# tail.net
KiCad netlist of a schematic drawn in EAGLE
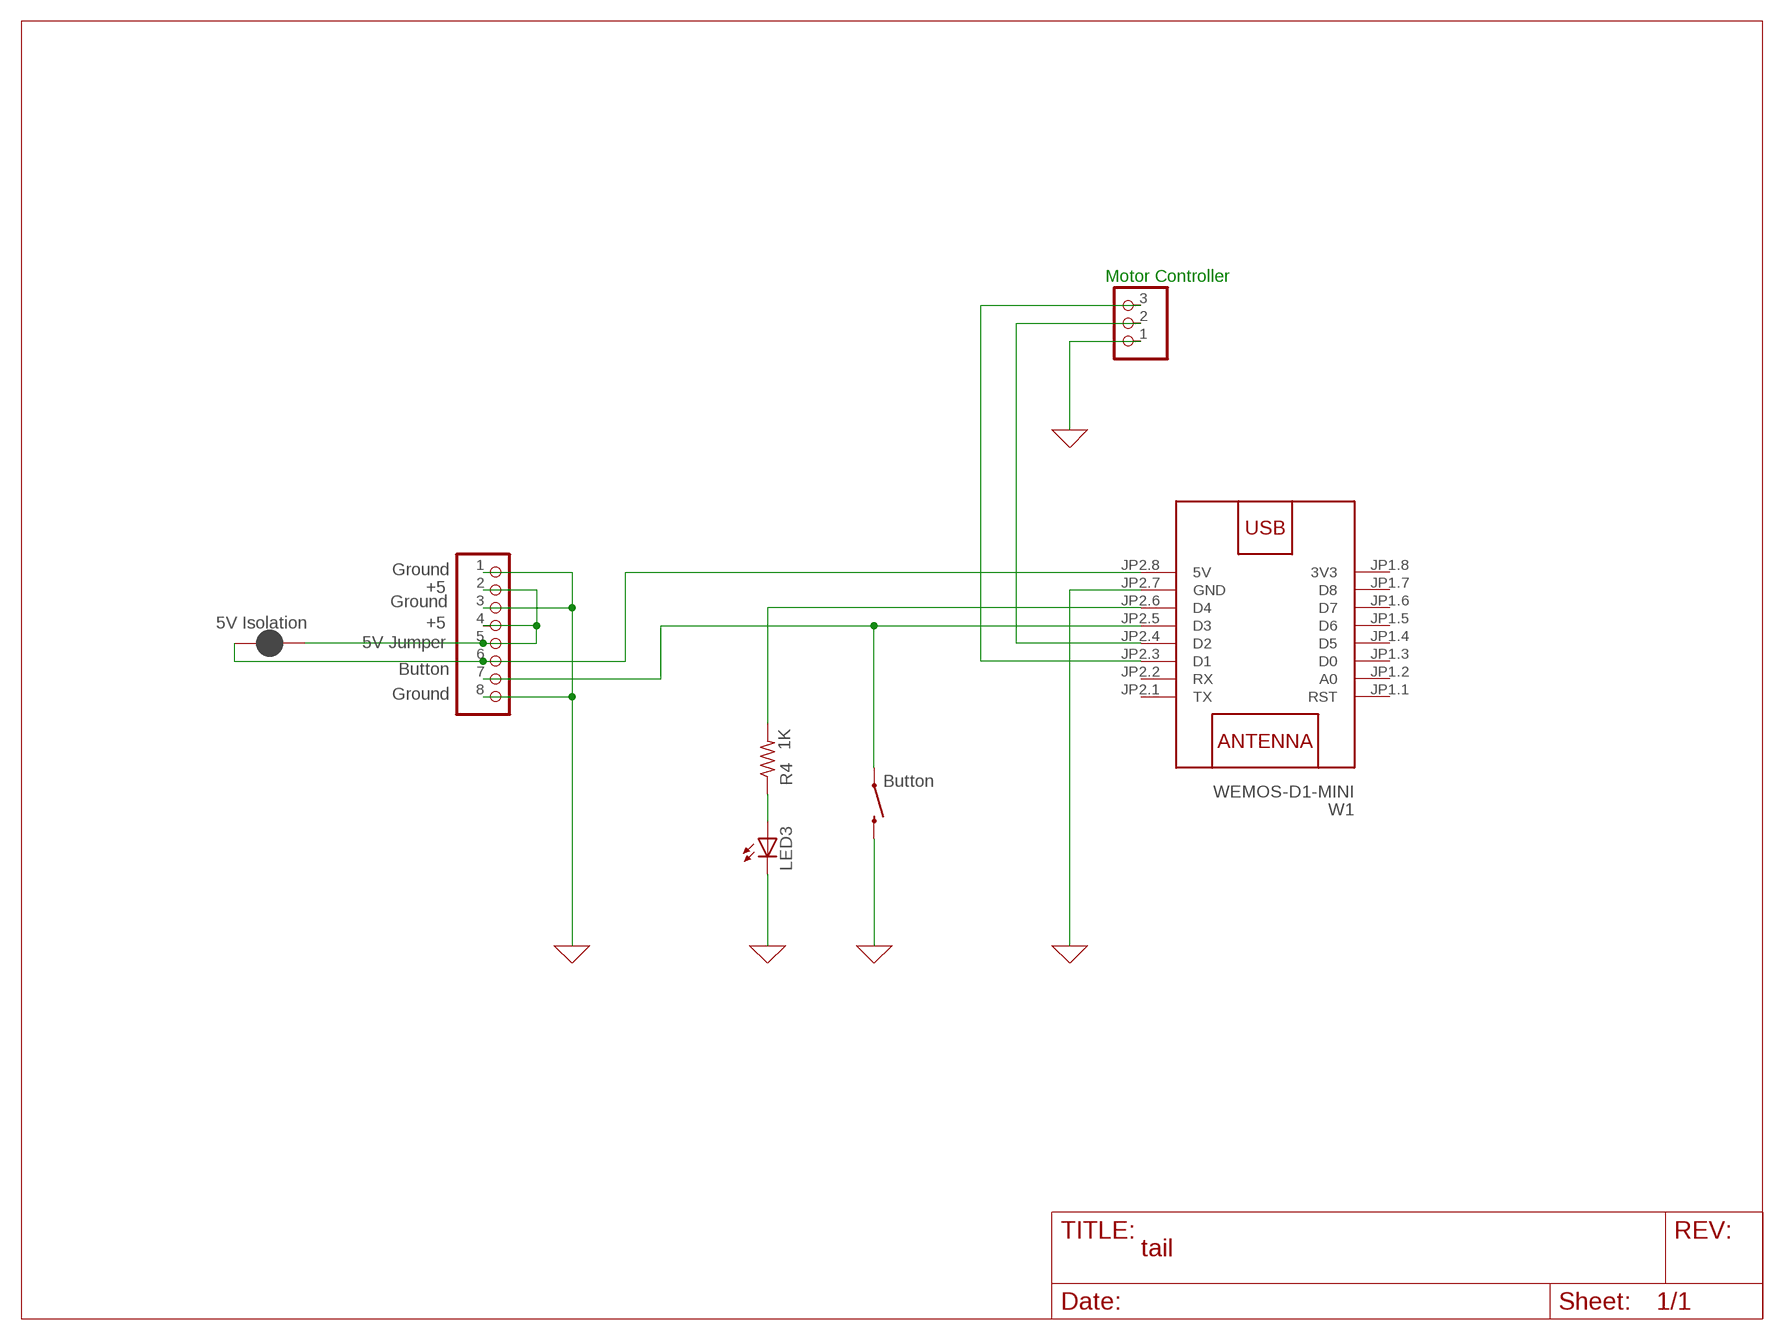
[diagram p0: schematic, sheet 1]

(export (version "E")
  (design (tool "Eeschema 10.0.6"))
  (components
    (comp (ref "JP1")
      (value "PINHD-1X8BIG")
      (footprint "eagle-import:1X08-BIG")
      (libsource (lib "eagle-import") (part "PINHD-1X8BIG"))
    )
    (comp (ref "JP2")
      (value "PINHD-1X3")
      (footprint "eagle-import:1X03")
      (libsource (lib "eagle-import") (part "PINHD-1X3"))
    )
    (comp (ref "JP3")
      (value "JUMPER-SMT_2_NC_PASTE_NO-SILK")
      (footprint "eagle-import:SMT-JUMPER_2_NC_PASTE_NO-SILK")
      (libsource (lib "eagle-import") (part "JUMPER-SMT_2_NC_PASTE_NO-SILK"))
    )
    (comp (ref "LED3")
      (value "LED5MM")
      (footprint "eagle-import:LED5MM")
      (libsource (lib "eagle-import") (part "LED5MM"))
    )
    (comp (ref "R4")
      (value "1K")
      (footprint "eagle-import:0207_10")
      (libsource (lib "eagle-import") (part "R-US_0207/10"))
    )
    (comp (ref "S1")
      (value "MOMENTARY-SWITCH-SPST-PTH-6.0MM")
      (footprint "eagle-import:TACTILE_SWITCH_PTH_6.0MM")
      (libsource (lib "eagle-import") (part "MOMENTARY-SWITCH-SPST-PTH-6.0MM"))
    )
    (comp (ref "W1")
      (value "WEMOS-D1-MINI")
      (footprint "eagle-import:WEMOS-D1-MINI")
      (libsource (lib "eagle-import") (part "WEMOS-D1-MINI"))
    )
  )
  (nets
    (net (code "1") (name "/3V3") (class "Default")
      (node (ref "W1") (pin "JP1.8") (pinfunction "3V3_JP1.8") (pintype "power_in"))
    )
    (net (code "2") (name "GND") (class "Default")
      (node (ref "JP1") (pin "1") (pinfunction "1_1") (pintype "passive"))
      (node (ref "JP1") (pin "3") (pinfunction "3_3") (pintype "passive"))
      (node (ref "JP1") (pin "8") (pinfunction "8_8") (pintype "passive"))
      (node (ref "JP2") (pin "1") (pinfunction "1_1") (pintype "passive"))
      (node (ref "LED3") (pin "K") (pinfunction "C_K") (pintype "passive"))
      (node (ref "S1") (pin "3") (pinfunction "2_3") (pintype "passive"))
      (node (ref "W1") (pin "JP2.7") (pinfunction "GND_JP2.7") (pintype "power_in"))
    )
    (net (code "3") (name "Net-(JP1-Pad2)") (class "Default")
      (node (ref "JP1") (pin "2") (pinfunction "2_2") (pintype "passive"))
      (node (ref "JP1") (pin "4") (pinfunction "4_4") (pintype "passive"))
      (node (ref "JP1") (pin "5") (pinfunction "5_5") (pintype "passive"))
      (node (ref "JP3") (pin "2") (pinfunction "2_2") (pintype "passive"))
    )
    (net (code "4") (name "Net-(LED3-PadA)") (class "Default")
      (node (ref "LED3") (pin "A") (pinfunction "A_A") (pintype "passive"))
      (node (ref "R4") (pin "1") (pinfunction "1_1") (pintype "passive"))
    )
    (net (code "5") (name "Net-(W1-5V)") (class "Default")
      (node (ref "JP1") (pin "6") (pinfunction "6_6") (pintype "passive"))
      (node (ref "JP3") (pin "1") (pinfunction "1_1") (pintype "passive"))
      (node (ref "W1") (pin "JP2.8") (pinfunction "5V_JP2.8") (pintype "power_in"))
    )
    (net (code "6") (name "Net-(W1-D1)") (class "Default")
      (node (ref "JP2") (pin "3") (pinfunction "3_3") (pintype "passive"))
      (node (ref "W1") (pin "JP2.3") (pinfunction "D1_JP2.3") (pintype "bidirectional"))
    )
    (net (code "7") (name "Net-(W1-D2)") (class "Default")
      (node (ref "JP2") (pin "2") (pinfunction "2_2") (pintype "passive"))
      (node (ref "W1") (pin "JP2.4") (pinfunction "D2_JP2.4") (pintype "bidirectional"))
    )
    (net (code "8") (name "Net-(W1-D3)") (class "Default")
      (node (ref "JP1") (pin "7") (pinfunction "7_7") (pintype "passive"))
      (node (ref "S1") (pin "1") (pinfunction "1_1") (pintype "passive"))
      (node (ref "W1") (pin "JP2.5") (pinfunction "D3_JP2.5") (pintype "bidirectional"))
    )
    (net (code "9") (name "Net-(W1-D4)") (class "Default")
      (node (ref "R4") (pin "2") (pinfunction "2_2") (pintype "passive"))
      (node (ref "W1") (pin "JP2.6") (pinfunction "D4_JP2.6") (pintype "bidirectional"))
    )
    (net (code "10") (name "unconnected-(W1-A0-PadJP1.2)") (class "Default")
      (node (ref "W1") (pin "JP1.2") (pinfunction "A0_JP1.2") (pintype "bidirectional"))
    )
    (net (code "11") (name "unconnected-(W1-D0-PadJP1.3)") (class "Default")
      (node (ref "W1") (pin "JP1.3") (pinfunction "D0_JP1.3") (pintype "bidirectional"))
    )
    (net (code "12") (name "unconnected-(W1-D5-PadJP1.4)") (class "Default")
      (node (ref "W1") (pin "JP1.4") (pinfunction "D5_JP1.4") (pintype "bidirectional"))
    )
    (net (code "13") (name "unconnected-(W1-D6-PadJP1.5)") (class "Default")
      (node (ref "W1") (pin "JP1.5") (pinfunction "D6_JP1.5") (pintype "bidirectional"))
    )
    (net (code "14") (name "unconnected-(W1-D7-PadJP1.6)") (class "Default")
      (node (ref "W1") (pin "JP1.6") (pinfunction "D7_JP1.6") (pintype "bidirectional"))
    )
    (net (code "15") (name "unconnected-(W1-D8-PadJP1.7)") (class "Default")
      (node (ref "W1") (pin "JP1.7") (pinfunction "D8_JP1.7") (pintype "bidirectional"))
    )
    (net (code "16") (name "unconnected-(W1-RST-PadJP1.1)") (class "Default")
      (node (ref "W1") (pin "JP1.1") (pinfunction "RST_JP1.1") (pintype "bidirectional"))
    )
    (net (code "17") (name "unconnected-(W1-RX-PadJP2.2)") (class "Default")
      (node (ref "W1") (pin "JP2.2") (pinfunction "RX_JP2.2") (pintype "bidirectional"))
    )
    (net (code "18") (name "unconnected-(W1-TX-PadJP2.1)") (class "Default")
      (node (ref "W1") (pin "JP2.1") (pinfunction "TX_JP2.1") (pintype "bidirectional"))
    )
  )
)
